# main.net
KiCad netlist of a schematic drawn in Altium Designer
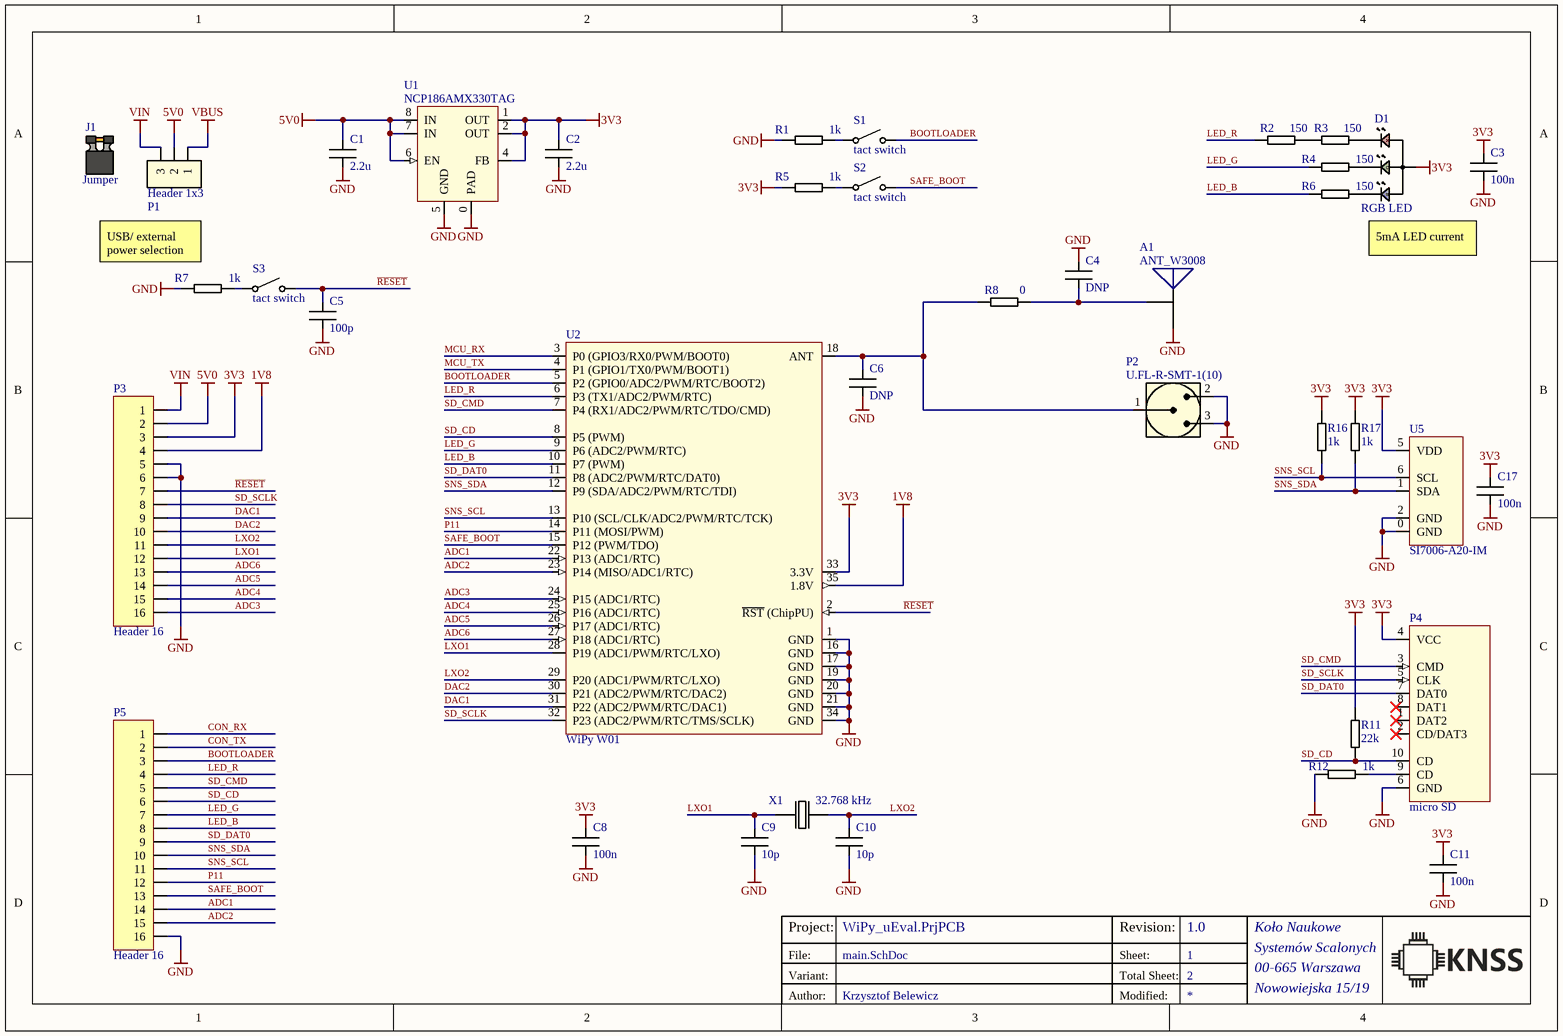
[diagram p0: main.SchDoc]

(export (version "E")
  (design (tool "Eeschema 10.0.6"))
  (components
    (comp (ref "A1")
      (value "ANT_W3008")
      (footprint "W3008")
      (description "Bluetooth / WLAN / WiFi  Ceramic Chip Antenna W x L x H (3.2 x 1.6 x 1.1 mm)")
      (libsource (lib "LIBRARY_SCH") (part "ANT_W3008"))
    )
    (comp (ref "C1")
      (value "2.2u")
      (footprint "CAPC1005N")
      (description "0402 SMD Capacitor")
      (fields (field (name "TOLERANCE") "10%") (field (name "Comment") "Capacitor"))
      (libsource (lib "RLC") (part "Capacitor"))
    )
    (comp (ref "C2")
      (value "2.2u")
      (footprint "CAPC1005N")
      (description "0402 SMD Capacitor")
      (fields (field (name "TOLERANCE") "10%") (field (name "Comment") "Capacitor"))
      (libsource (lib "RLC") (part "Capacitor"))
    )
    (comp (ref "C3")
      (value "100n")
      (footprint "CAPC1005N")
      (description "0402 SMD Capacitor")
      (fields (field (name "TOLERANCE") "10%"))
      (libsource (lib "RLC") (part "Capacitor"))
    )
    (comp (ref "C4")
      (value "DNP")
      (footprint "CAPC1005N")
      (description "0402 SMD Capacitor")
      (fields (field (name "Comment") "Capacitor"))
      (libsource (lib "RLC") (part "Capacitor"))
    )
    (comp (ref "C5")
      (value "100p")
      (footprint "CAPC1005N")
      (description "0402 SMD Capacitor")
      (fields (field (name "TOLERANCE") "10%"))
      (libsource (lib "RLC") (part "Capacitor"))
    )
    (comp (ref "C6")
      (value "DNP")
      (footprint "CAPC1005N")
      (description "0402 SMD Capacitor")
      (fields (field (name "Comment") "Capacitor"))
      (libsource (lib "RLC") (part "Capacitor"))
    )
    (comp (ref "C8")
      (value "100n")
      (footprint "CAPC1005N")
      (description "0402 SMD Capacitor")
      (fields (field (name "TOLERANCE") "10%"))
      (libsource (lib "RLC") (part "Capacitor"))
    )
    (comp (ref "C9")
      (value "10p")
      (footprint "CAPC1005N")
      (description "0402 SMD Capacitor")
      (fields (field (name "TOLERANCE") "5%"))
      (libsource (lib "RLC") (part "Capacitor"))
    )
    (comp (ref "C10")
      (value "10p")
      (footprint "CAPC1005N")
      (description "0402 SMD Capacitor")
      (fields (field (name "TOLERANCE") "5%"))
      (libsource (lib "RLC") (part "Capacitor"))
    )
    (comp (ref "C11")
      (value "100n")
      (footprint "CAPC1005N")
      (description "0402 SMD Capacitor")
      (fields (field (name "TOLERANCE") "10%"))
      (libsource (lib "RLC") (part "Capacitor"))
    )
    (comp (ref "C17")
      (value "100n")
      (footprint "CAPC1005N")
      (description "0402 SMD Capacitor")
      (fields (field (name "TOLERANCE") "10%"))
      (libsource (lib "RLC") (part "Capacitor"))
    )
    (comp (ref "D1")
      (value "RGB LED")
      (footprint "PLCC-4")
      (description "LED; SMD; 3528,PLCC4; RGB; 3,5x2,8x1,9mm; 115°; 20mA; Common anode")
      (libsource (lib "Broadcom_LED") (part "ASMB-MTB1-0A3A2"))
    )
    (comp (ref "J1")
      (value "Jumper")
      (footprint "JUMPER-B")
      (description "1x2, 2.54mm Black header jumper")
      (libsource (lib "Ninigi_Jumpers") (part "Header Jumper Black"))
    )
    (comp (ref "P1")
      (value "Header 1x3")
      (footprint "Header 1x3, Male, 2.54mm, Straight, THT")
      (description "Pin header, 1x3, 2.54mm")
      (libsource (lib "Header") (part "Header 1x3"))
    )
    (comp (ref "P2")
      (value "U.FL-R-SMT-1(10)")
      (footprint "U.FL-R-SMT-1(10)")
      (description "Hirose UFL connector")
      (libsource (lib "Hirose") (part "U.FL-R-SMT-1(10)"))
    )
    (comp (ref "P3")
      (value "Header 16")
      (footprint "HDR1X16")
      (description "Header, 16-Pin")
      (libsource (lib "Miscellaneous Connectors") (part "Header 16"))
    )
    (comp (ref "P4")
      (value "micro SD")
      (footprint "1140084168")
      (description "Memory Card Connectors Micro SD 8 Pin PCB Gold")
      (libsource (lib "Amphenol_uSD") (part "1140084168"))
    )
    (comp (ref "P5")
      (value "Header 16")
      (footprint "HDR1X16")
      (description "Header, 16-Pin")
      (libsource (lib "Miscellaneous Connectors") (part "Header 16"))
    )
    (comp (ref "R1")
      (value "1k")
      (footprint "RESC1005N")
      (description "0402 Film SMD Resistor")
      (fields (field (name "TOLERANCE") "1%") (field (name "POWER") "0.1W"))
      (libsource (lib "RLC") (part "Resistor"))
    )
    (comp (ref "R2")
      (value "150")
      (footprint "RESC1005N")
      (description "0402 Film SMD Resistor")
      (fields (field (name "TOLERANCE") "1%") (field (name "POWER") "0.1W"))
      (libsource (lib "RLC") (part "Resistor"))
    )
    (comp (ref "R3")
      (value "150")
      (footprint "RESC1005N")
      (description "0402 Film SMD Resistor")
      (fields (field (name "TOLERANCE") "1%") (field (name "POWER") "0.1W"))
      (libsource (lib "RLC") (part "Resistor"))
    )
    (comp (ref "R4")
      (value "150")
      (footprint "RESC1005N")
      (description "0402 Film SMD Resistor")
      (fields (field (name "TOLERANCE") "1%") (field (name "POWER") "0.1W"))
      (libsource (lib "RLC") (part "Resistor"))
    )
    (comp (ref "R5")
      (value "1k")
      (footprint "RESC1005N")
      (description "0402 Film SMD Resistor")
      (fields (field (name "TOLERANCE") "1%") (field (name "POWER") "0.1W"))
      (libsource (lib "RLC") (part "Resistor"))
    )
    (comp (ref "R6")
      (value "150")
      (footprint "RESC1005N")
      (description "0402 Film SMD Resistor")
      (fields (field (name "TOLERANCE") "1%") (field (name "POWER") "0.1W"))
      (libsource (lib "RLC") (part "Resistor"))
    )
    (comp (ref "R7")
      (value "1k")
      (footprint "RESC1005N")
      (description "0402 Film SMD Resistor")
      (fields (field (name "TOLERANCE") "1%") (field (name "POWER") "0.1W"))
      (libsource (lib "RLC") (part "Resistor"))
    )
    (comp (ref "R8")
      (value "0")
      (footprint "RESC1005N")
      (description "0402 Film SMD Resistor")
      (fields (field (name "TOLERANCE") "1%") (field (name "POWER") "0.1W"))
      (libsource (lib "RLC") (part "Resistor"))
    )
    (comp (ref "R11")
      (value "22k")
      (footprint "RESC1005N")
      (description "0402 Film SMD Resistor")
      (fields (field (name "TOLERANCE") "1%") (field (name "POWER") "0.1W"))
      (libsource (lib "RLC") (part "Resistor"))
    )
    (comp (ref "R12")
      (value "1k")
      (footprint "RESC1005N")
      (description "0402 Film SMD Resistor")
      (fields (field (name "TOLERANCE") "1%") (field (name "POWER") "0.1W"))
      (libsource (lib "RLC") (part "Resistor"))
    )
    (comp (ref "R16")
      (value "1k")
      (footprint "RESC1005N")
      (description "0402 Film SMD Resistor")
      (fields (field (name "TOLERANCE") "1%") (field (name "POWER") "0.1W"))
      (libsource (lib "RLC") (part "Resistor"))
    )
    (comp (ref "R17")
      (value "1k")
      (footprint "RESC1005N")
      (description "0402 Film SMD Resistor")
      (fields (field (name "TOLERANCE") "1%") (field (name "POWER") "0.1W"))
      (libsource (lib "RLC") (part "Resistor"))
    )
    (comp (ref "S1")
      (value "tact switch")
      (footprint "1301.9319")
      (description "TACT; SPST-NO; 2 position; 0,05A/12VDC; SMT")
      (libsource (lib "Schurter_Switches") (part "1301.9319"))
    )
    (comp (ref "S2")
      (value "tact switch")
      (footprint "1301.9319")
      (description "TACT; SPST-NO; 2 position; 0,05A/12VDC; SMT")
      (libsource (lib "Schurter_Switches") (part "1301.9319"))
    )
    (comp (ref "S3")
      (value "tact switch")
      (footprint "1301.9319")
      (description "TACT; SPST-NO; 2 position; 0,05A/12VDC; SMT")
      (libsource (lib "Schurter_Switches") (part "1301.9319"))
    )
    (comp (ref "U1")
      (value "NCP186AMX330TAG")
      (footprint "XDFN8")
      (description "3.3V 1A LDO Voltage Regulator")
      (libsource (lib "Power_Supervisors") (part "NCP186AMX330TAG"))
    )
    (comp (ref "U2")
      (value "WiPy W01")
      (footprint "WiPy_W01")
      (description "Wireless LAN Module, I2C, I2S, SPI, UART, M2M, Internet of Things")
      (libsource (lib "WiPy") (part "W01"))
    )
    (comp (ref "U5")
      (value "SI7006-A20-IM")
      (footprint "DFN6")
      (description "I2C HUMIDITY AND TEMPERATURE SENSOR")
      (libsource (lib "SiliconLabs") (part "SI7006-A20-IM"))
    )
    (comp (ref "X1")
      (value "32.768 kHz")
      (footprint "MC-306")
      (description "Standard Clock Oscillators 32,768kHz 20ppm -40C +85C")
      (libsource (lib "EPSON_Oscillators") (part "MC306 32.768000KHZ 12.5PF"))
    )
  )
  (nets
    (net (code "1") (name "/ADC1") (class "Default")
      (node (ref "P5") (pin "14") (pinfunction "14_14") (pintype "passive"))
      (node (ref "U2") (pin "22") (pinfunction "P13_(ADC1/RTC)_22") (pintype "input"))
    )
    (net (code "2") (name "/ADC2") (class "Default")
      (node (ref "P5") (pin "15") (pinfunction "15_15") (pintype "passive"))
      (node (ref "U2") (pin "23") (pinfunction "P14_(MISO/ADC1/RTC)_23") (pintype "input"))
    )
    (net (code "3") (name "/ADC3") (class "Default")
      (node (ref "P3") (pin "16") (pinfunction "16_16") (pintype "passive"))
      (node (ref "U2") (pin "24") (pinfunction "P15_(ADC1/RTC)_24") (pintype "input"))
    )
    (net (code "4") (name "/ADC4") (class "Default")
      (node (ref "P3") (pin "15") (pinfunction "15_15") (pintype "passive"))
      (node (ref "U2") (pin "25") (pinfunction "P16_(ADC1/RTC)_25") (pintype "input"))
    )
    (net (code "5") (name "/ADC5") (class "Default")
      (node (ref "P3") (pin "14") (pinfunction "14_14") (pintype "passive"))
      (node (ref "U2") (pin "26") (pinfunction "P17_(ADC1/RTC)_26") (pintype "input"))
    )
    (net (code "6") (name "/ADC6") (class "Default")
      (node (ref "P3") (pin "13") (pinfunction "13_13") (pintype "passive"))
      (node (ref "U2") (pin "27") (pinfunction "P18_(ADC1/RTC)_27") (pintype "input"))
    )
    (net (code "7") (name "/BOOTLOADER") (class "Default")
      (node (ref "P5") (pin "3") (pinfunction "3_3") (pintype "passive"))
      (node (ref "S1") (pin "2") (pinfunction "2_2") (pintype "passive"))
      (node (ref "U2") (pin "5") (pinfunction "P2_(GPIO0/ADC2/PWM/RTC/BOOT2)_5") (pintype "bidirectional"))
    )
    (net (code "8") (name "/CON_RX") (class "Default")
      (node (ref "P5") (pin "1") (pinfunction "1_1") (pintype "passive"))
    )
    (net (code "9") (name "/CON_TX") (class "Default")
      (node (ref "P5") (pin "2") (pinfunction "2_2") (pintype "passive"))
    )
    (net (code "10") (name "/DAC1") (class "Default")
      (node (ref "P3") (pin "9") (pinfunction "9_9") (pintype "passive"))
      (node (ref "U2") (pin "31") (pinfunction "P22_(ADC2/PWM/RTC/DAC1)_31") (pintype "bidirectional"))
    )
    (net (code "11") (name "/DAC2") (class "Default")
      (node (ref "P3") (pin "10") (pinfunction "10_10") (pintype "passive"))
      (node (ref "U2") (pin "30") (pinfunction "P21_(ADC2/PWM/RTC/DAC2)_30") (pintype "bidirectional"))
    )
    (net (code "12") (name "/LED_B") (class "Default")
      (node (ref "P5") (pin "8") (pinfunction "8_8") (pintype "passive"))
      (node (ref "R6") (pin "2") (pinfunction "2_2") (pintype "passive"))
      (node (ref "U2") (pin "10") (pinfunction "P7_(PWM)_10") (pintype "bidirectional"))
    )
    (net (code "13") (name "/LED_G") (class "Default")
      (node (ref "P5") (pin "7") (pinfunction "7_7") (pintype "passive"))
      (node (ref "R4") (pin "2") (pinfunction "2_2") (pintype "passive"))
      (node (ref "U2") (pin "9") (pinfunction "P6_(ADC2/PWM/RTC)_9") (pintype "bidirectional"))
    )
    (net (code "14") (name "/LED_R") (class "Default")
      (node (ref "P5") (pin "4") (pinfunction "4_4") (pintype "passive"))
      (node (ref "R2") (pin "2") (pinfunction "2_2") (pintype "passive"))
      (node (ref "U2") (pin "6") (pinfunction "P3_(TX1/ADC2/PWM/RTC)_6") (pintype "bidirectional"))
    )
    (net (code "15") (name "/LXO1") (class "Default")
      (node (ref "C9") (pin "2") (pinfunction "2_2") (pintype "passive"))
      (node (ref "P3") (pin "12") (pinfunction "12_12") (pintype "passive"))
      (node (ref "U2") (pin "28") (pinfunction "P19_(ADC1/PWM/RTC/LXO)_28") (pintype "bidirectional"))
      (node (ref "X1") (pin "4") (pinfunction "4_4") (pintype "passive"))
    )
    (net (code "16") (name "/LXO2") (class "Default")
      (node (ref "C10") (pin "2") (pinfunction "2_2") (pintype "passive"))
      (node (ref "P3") (pin "11") (pinfunction "11_11") (pintype "passive"))
      (node (ref "U2") (pin "29") (pinfunction "P20_(ADC1/PWM/RTC/LXO)_29") (pintype "bidirectional"))
      (node (ref "X1") (pin "1") (pinfunction "1_1") (pintype "passive"))
    )
    (net (code "17") (name "/MCU_RX") (class "Default")
      (node (ref "U2") (pin "3") (pinfunction "P0_(GPIO3/RX0/PWM/BOOT0)_3") (pintype "bidirectional"))
    )
    (net (code "18") (name "/MCU_TX") (class "Default")
      (node (ref "U2") (pin "4") (pinfunction "P1_(GPIO1/TX0/PWM/BOOT1)_4") (pintype "bidirectional"))
    )
    (net (code "19") (name "/P11") (class "Default")
      (node (ref "P5") (pin "12") (pinfunction "12_12") (pintype "passive"))
      (node (ref "U2") (pin "14") (pinfunction "P11_(MOSI/PWM)_14") (pintype "bidirectional"))
    )
    (net (code "20") (name "/SAFE_BOOT") (class "Default")
      (node (ref "P5") (pin "13") (pinfunction "13_13") (pintype "passive"))
      (node (ref "S2") (pin "2") (pinfunction "2_2") (pintype "passive"))
      (node (ref "U2") (pin "15") (pinfunction "P12_(PWM/TDO)_15") (pintype "bidirectional"))
    )
    (net (code "21") (name "/SD_CD") (class "Default")
      (node (ref "P4") (pin "10") (pinfunction "CD_10") (pintype "passive"))
      (node (ref "P5") (pin "6") (pinfunction "6_6") (pintype "passive"))
      (node (ref "R11") (pin "1") (pinfunction "1_1") (pintype "passive"))
      (node (ref "U2") (pin "8") (pinfunction "P5_(PWM)_8") (pintype "bidirectional"))
    )
    (net (code "22") (name "/SD_CMD") (class "Default")
      (node (ref "P4") (pin "3") (pinfunction "CMD_3") (pintype "input"))
      (node (ref "P5") (pin "5") (pinfunction "5_5") (pintype "passive"))
      (node (ref "U2") (pin "7") (pinfunction "P4_(RX1/ADC2/PWM/RTC/TDO/CMD)_7") (pintype "bidirectional"))
    )
    (net (code "23") (name "/SD_DAT0") (class "Default")
      (node (ref "P4") (pin "7") (pinfunction "DAT0_7") (pintype "bidirectional"))
      (node (ref "P5") (pin "9") (pinfunction "9_9") (pintype "passive"))
      (node (ref "U2") (pin "11") (pinfunction "P8_(ADC2/PWM/RTC/DAT0)_11") (pintype "bidirectional"))
    )
    (net (code "24") (name "/SD_SCLK") (class "Default")
      (node (ref "P3") (pin "8") (pinfunction "8_8") (pintype "passive"))
      (node (ref "P4") (pin "5") (pinfunction "CLK_5") (pintype "input"))
      (node (ref "U2") (pin "32") (pinfunction "P23_(ADC2/PWM/RTC/TMS/SCLK)_32") (pintype "bidirectional"))
    )
    (net (code "25") (name "/SNS_SCL") (class "Default")
      (node (ref "P5") (pin "11") (pinfunction "11_11") (pintype "passive"))
      (node (ref "R16") (pin "2") (pinfunction "2_2") (pintype "passive"))
      (node (ref "U2") (pin "13") (pinfunction "P10_(SCL/CLK/ADC2/PWM/RTC/TCK)_13") (pintype "bidirectional"))
      (node (ref "U5") (pin "6") (pinfunction "SCL_6") (pintype "bidirectional"))
    )
    (net (code "26") (name "/SNS_SDA") (class "Default")
      (node (ref "P5") (pin "10") (pinfunction "10_10") (pintype "passive"))
      (node (ref "R17") (pin "2") (pinfunction "2_2") (pintype "passive"))
      (node (ref "U2") (pin "12") (pinfunction "P9_(SDA/ADC2/PWM/RTC/TDI)_12") (pintype "bidirectional"))
      (node (ref "U5") (pin "1") (pinfunction "SDA_1") (pintype "bidirectional"))
    )
    (net (code "27") (name "/~{RESET}") (class "Default")
      (node (ref "C5") (pin "2") (pinfunction "2_2") (pintype "passive"))
      (node (ref "P3") (pin "7") (pinfunction "7_7") (pintype "passive"))
      (node (ref "S3") (pin "2") (pinfunction "2_2") (pintype "passive"))
      (node (ref "U2") (pin "2") (pinfunction "~{RST}_(ChipPU)_2") (pintype "input"))
    )
    (net (code "28") (name "1V8") (class "Default")
      (node (ref "P3") (pin "4") (pinfunction "4_4") (pintype "passive"))
      (node (ref "U2") (pin "35") (pinfunction "1.8V_35") (pintype "output"))
    )
    (net (code "29") (name "3V3") (class "Default")
      (node (ref "C11") (pin "2") (pinfunction "2_2") (pintype "passive"))
      (node (ref "C17") (pin "2") (pinfunction "2_2") (pintype "passive"))
      (node (ref "C2") (pin "2") (pinfunction "2_2") (pintype "passive"))
      (node (ref "C3") (pin "2") (pinfunction "2_2") (pintype "passive"))
      (node (ref "C8") (pin "2") (pinfunction "2_2") (pintype "passive"))
      (node (ref "D1") (pin "4") (pinfunction "A_4") (pintype "passive"))
      (node (ref "P3") (pin "3") (pinfunction "3_3") (pintype "passive"))
      (node (ref "P4") (pin "4") (pinfunction "VCC_4") (pintype "power_in"))
      (node (ref "R11") (pin "2") (pinfunction "2_2") (pintype "passive"))
      (node (ref "R16") (pin "1") (pinfunction "1_1") (pintype "passive"))
      (node (ref "R17") (pin "1") (pinfunction "1_1") (pintype "passive"))
      (node (ref "R5") (pin "2") (pinfunction "2_2") (pintype "passive"))
      (node (ref "U1") (pin "1") (pinfunction "OUT_1") (pintype "power_in"))
      (node (ref "U1") (pin "2") (pinfunction "OUT_2") (pintype "power_in"))
      (node (ref "U1") (pin "4") (pinfunction "FB_4") (pintype "power_in"))
      (node (ref "U2") (pin "33") (pinfunction "3.3V_33") (pintype "power_in"))
      (node (ref "U5") (pin "5") (pinfunction "VDD_5") (pintype "power_in"))
    )
    (net (code "30") (name "5V0") (class "Default")
      (node (ref "C1") (pin "2") (pinfunction "2_2") (pintype "passive"))
      (node (ref "P1") (pin "2") (pinfunction "2_2") (pintype "passive"))
      (node (ref "P3") (pin "2") (pinfunction "2_2") (pintype "passive"))
      (node (ref "U1") (pin "6") (pinfunction "EN_6") (pintype "input"))
      (node (ref "U1") (pin "7") (pinfunction "IN_7") (pintype "power_in"))
      (node (ref "U1") (pin "8") (pinfunction "IN_8") (pintype "power_in"))
    )
    (net (code "31") (name "GND") (class "Default")
      (node (ref "A1") (pin "2") (pinfunction "GND_2") (pintype "passive"))
      (node (ref "C1") (pin "1") (pinfunction "1_1") (pintype "passive"))
      (node (ref "C10") (pin "1") (pinfunction "1_1") (pintype "passive"))
      (node (ref "C11") (pin "1") (pinfunction "1_1") (pintype "passive"))
      (node (ref "C17") (pin "1") (pinfunction "1_1") (pintype "passive"))
      (node (ref "C2") (pin "1") (pinfunction "1_1") (pintype "passive"))
      (node (ref "C3") (pin "1") (pinfunction "1_1") (pintype "passive"))
      (node (ref "C4") (pin "2") (pinfunction "2_2") (pintype "passive"))
      (node (ref "C5") (pin "1") (pinfunction "1_1") (pintype "passive"))
      (node (ref "C6") (pin "1") (pinfunction "1_1") (pintype "passive"))
      (node (ref "C8") (pin "1") (pinfunction "1_1") (pintype "passive"))
      (node (ref "C9") (pin "1") (pinfunction "1_1") (pintype "passive"))
      (node (ref "P2") (pin "2") (pinfunction "2_2") (pintype "passive"))
      (node (ref "P2") (pin "3") (pinfunction "3_3") (pintype "passive"))
      (node (ref "P3") (pin "5") (pinfunction "5_5") (pintype "passive"))
      (node (ref "P3") (pin "6") (pinfunction "6_6") (pintype "passive"))
      (node (ref "P4") (pin "6") (pinfunction "GND_6") (pintype "power_in"))
      (node (ref "P5") (pin "16") (pinfunction "16_16") (pintype "passive"))
      (node (ref "R1") (pin "2") (pinfunction "2_2") (pintype "passive"))
      (node (ref "R12") (pin "2") (pinfunction "2_2") (pintype "passive"))
      (node (ref "R7") (pin "2") (pinfunction "2_2") (pintype "passive"))
      (node (ref "U1") (pin "0") (pinfunction "PAD_0") (pintype "power_in"))
      (node (ref "U1") (pin "5") (pinfunction "GND_5") (pintype "power_in"))
      (node (ref "U2") (pin "1") (pinfunction "GND_1") (pintype "power_in"))
      (node (ref "U2") (pin "16") (pinfunction "GND_16") (pintype "power_in"))
      (node (ref "U2") (pin "17") (pinfunction "GND_17") (pintype "power_in"))
      (node (ref "U2") (pin "19") (pinfunction "GND_19") (pintype "power_in"))
      (node (ref "U2") (pin "20") (pinfunction "GND_20") (pintype "power_in"))
      (node (ref "U2") (pin "21") (pinfunction "GND_21") (pintype "power_in"))
      (node (ref "U2") (pin "34") (pinfunction "GND_34") (pintype "power_in"))
      (node (ref "U5") (pin "0") (pinfunction "GND_0") (pintype "power_in"))
      (node (ref "U5") (pin "2") (pinfunction "GND_2") (pintype "power_in"))
    )
    (net (code "32") (name "Net-(A1-SIG)") (class "Default")
      (node (ref "A1") (pin "1") (pinfunction "SIG_1") (pintype "passive"))
      (node (ref "C4") (pin "1") (pinfunction "1_1") (pintype "passive"))
      (node (ref "R8") (pin "1") (pinfunction "1_1") (pintype "passive"))
    )
    (net (code "33") (name "Net-(D1-CB)") (class "Default")
      (node (ref "D1") (pin "3") (pinfunction "CB_3") (pintype "passive"))
      (node (ref "R6") (pin "1") (pinfunction "1_1") (pintype "passive"))
    )
    (net (code "34") (name "Net-(D1-CG)") (class "Default")
      (node (ref "D1") (pin "2") (pinfunction "CG_2") (pintype "passive"))
      (node (ref "R4") (pin "1") (pinfunction "1_1") (pintype "passive"))
    )
    (net (code "35") (name "Net-(D1-CR)") (class "Default")
      (node (ref "D1") (pin "1") (pinfunction "CR_1") (pintype "passive"))
      (node (ref "R3") (pin "1") (pinfunction "1_1") (pintype "passive"))
    )
    (net (code "36") (name "Net-(P4-CD-Pad9)") (class "Default")
      (node (ref "P4") (pin "9") (pinfunction "CD_9") (pintype "passive"))
      (node (ref "R12") (pin "1") (pinfunction "1_1") (pintype "passive"))
    )
    (net (code "37") (name "Net-(R1-Pad1)") (class "Default")
      (node (ref "R1") (pin "1") (pinfunction "1_1") (pintype "passive"))
      (node (ref "S1") (pin "1") (pinfunction "1_1") (pintype "passive"))
    )
    (net (code "38") (name "Net-(R2-Pad1)") (class "Default")
      (node (ref "R2") (pin "1") (pinfunction "1_1") (pintype "passive"))
      (node (ref "R3") (pin "2") (pinfunction "2_2") (pintype "passive"))
    )
    (net (code "39") (name "Net-(R5-Pad1)") (class "Default")
      (node (ref "R5") (pin "1") (pinfunction "1_1") (pintype "passive"))
      (node (ref "S2") (pin "1") (pinfunction "1_1") (pintype "passive"))
    )
    (net (code "40") (name "Net-(R7-Pad1)") (class "Default")
      (node (ref "R7") (pin "1") (pinfunction "1_1") (pintype "passive"))
      (node (ref "S3") (pin "1") (pinfunction "1_1") (pintype "passive"))
    )
    (net (code "41") (name "Net-(U2-ANT)") (class "Default")
      (node (ref "C6") (pin "2") (pinfunction "2_2") (pintype "passive"))
      (node (ref "P2") (pin "1") (pinfunction "1_1") (pintype "passive"))
      (node (ref "R8") (pin "2") (pinfunction "2_2") (pintype "passive"))
      (node (ref "U2") (pin "18") (pinfunction "ANT_18") (pintype "bidirectional"))
    )
    (net (code "42") (name "VBUS") (class "Default")
      (node (ref "P1") (pin "1") (pinfunction "1_1") (pintype "passive"))
    )
    (net (code "43") (name "VIN") (class "Default")
      (node (ref "P1") (pin "3") (pinfunction "3_3") (pintype "passive"))
      (node (ref "P3") (pin "1") (pinfunction "1_1") (pintype "passive"))
    )
    (net (code "44") (name "unconnected-(P4-CD{slash}DAT3-Pad2)") (class "Default")
      (node (ref "P4") (pin "2") (pinfunction "CD/DAT3_2") (pintype "bidirectional+no_connect"))
    )
    (net (code "45") (name "unconnected-(P4-DAT1-Pad8)") (class "Default")
      (node (ref "P4") (pin "8") (pinfunction "DAT1_8") (pintype "bidirectional+no_connect"))
    )
    (net (code "46") (name "unconnected-(P4-DAT2-Pad1)") (class "Default")
      (node (ref "P4") (pin "1") (pinfunction "DAT2_1") (pintype "bidirectional+no_connect"))
    )
  )
)
